# HVIBDC.net
KiCad netlist of a schematic drawn in EAGLE
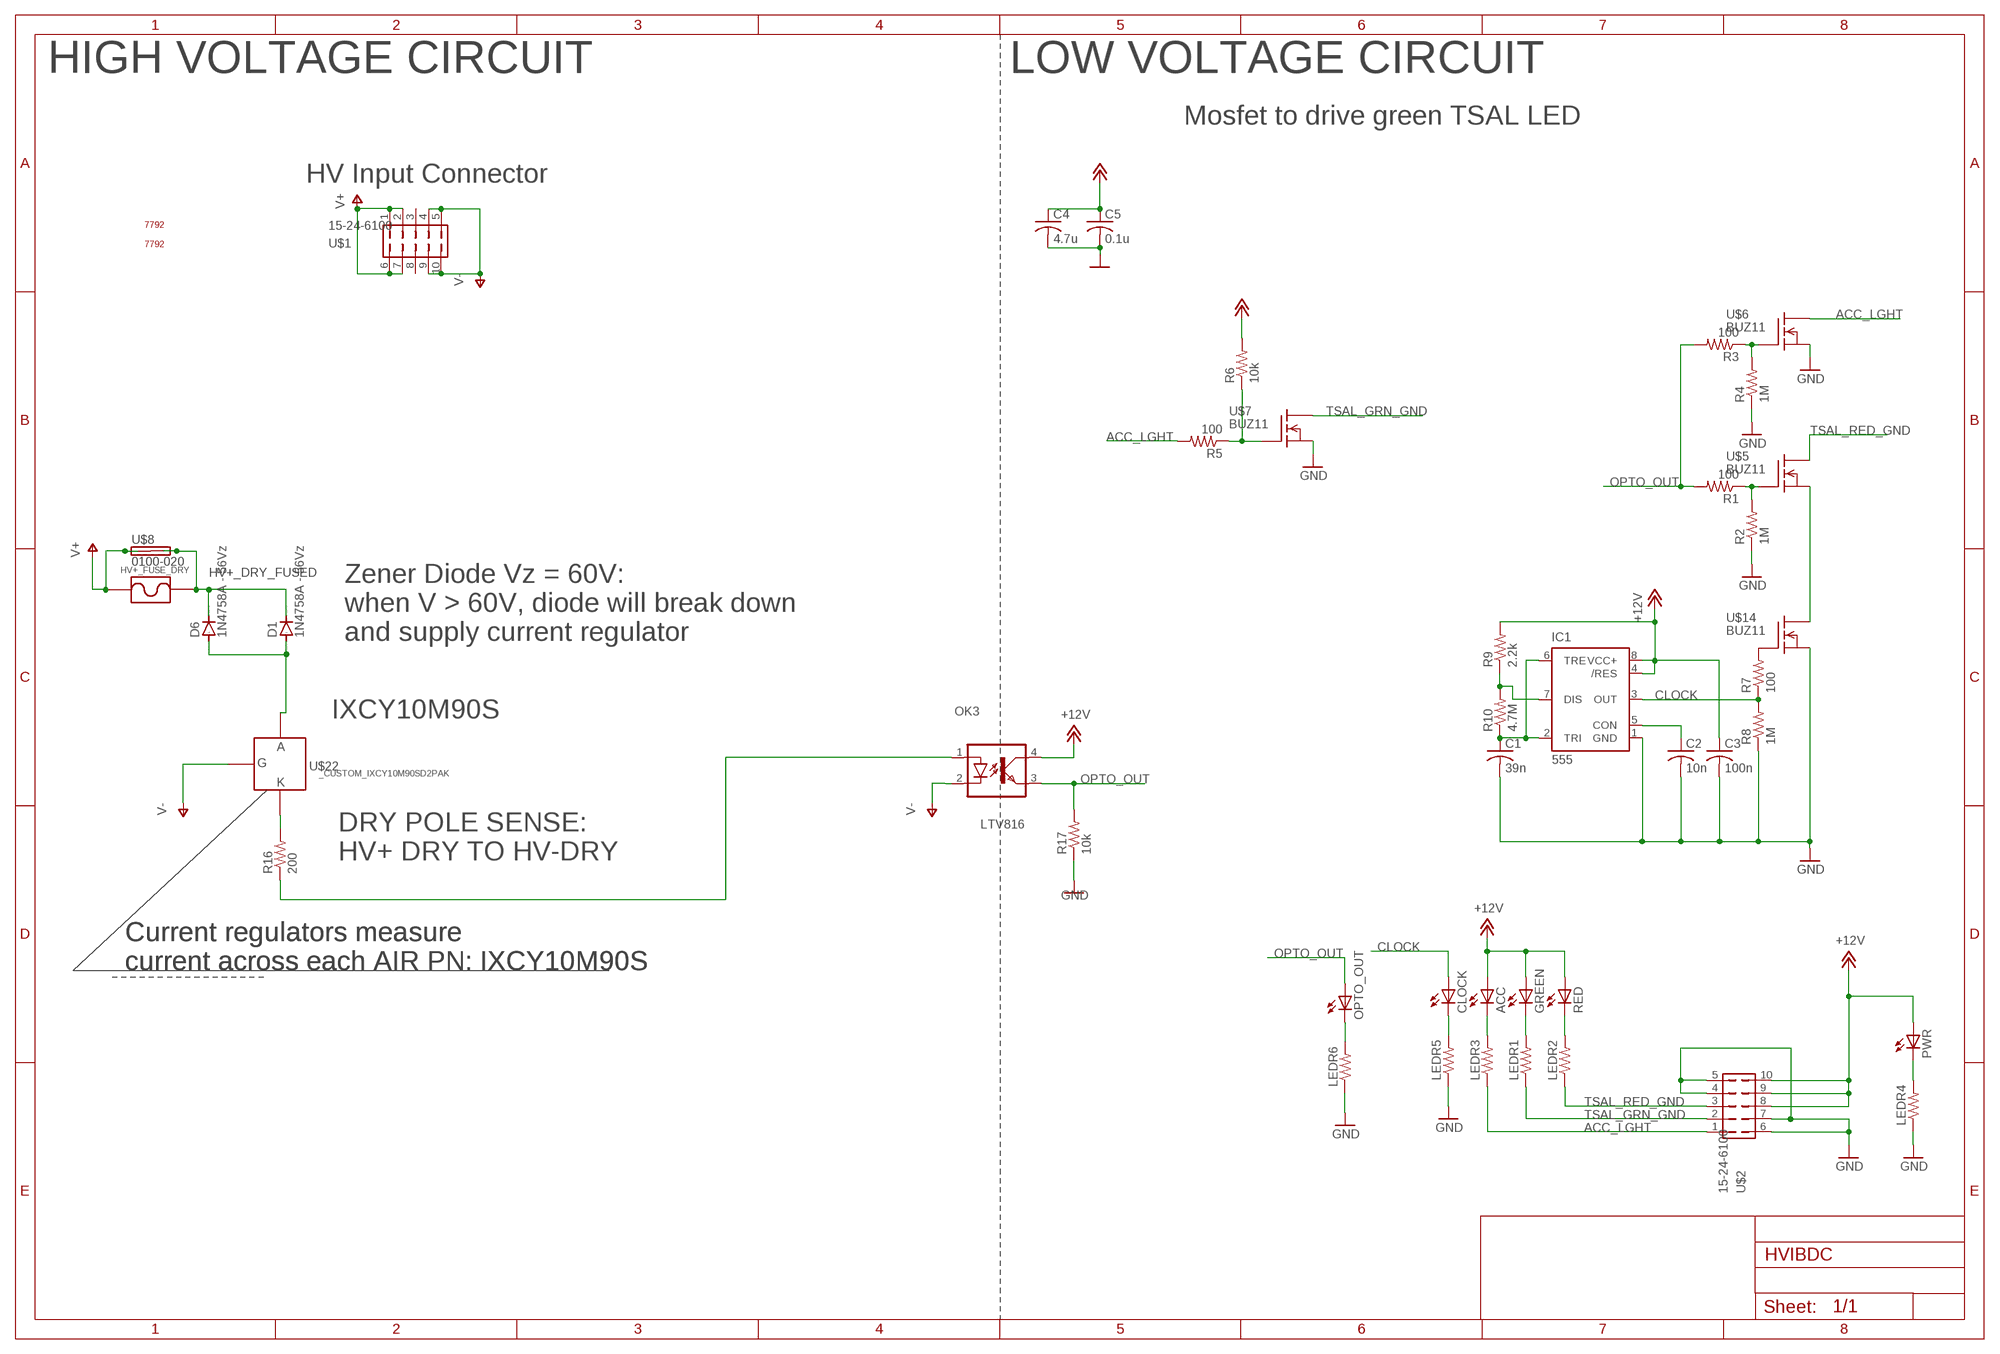
[diagram p0: schematic, sheet 1]

(export (version "E")
  (design (tool "Eeschema 10.0.6"))
  (components
    (comp (ref "ACC")
      (value "LEDCHIPLED_0805")
      (footprint "eagle-import:CHIPLED_0805")
      (libsource (lib "eagle-import") (part "LEDCHIPLED_0805"))
    )
    (comp (ref "C1")
      (value "39n")
      (footprint "eagle-import:C0805")
      (libsource (lib "eagle-import") (part "C-USC0805"))
    )
    (comp (ref "C2")
      (value "10n")
      (footprint "eagle-import:C0805")
      (libsource (lib "eagle-import") (part "C-USC0805"))
    )
    (comp (ref "C3")
      (value "100n")
      (footprint "eagle-import:C0805")
      (libsource (lib "eagle-import") (part "C-USC0805"))
    )
    (comp (ref "C4")
      (value "4.7u")
      (footprint "eagle-import:C0805")
      (libsource (lib "eagle-import") (part "C-USC0805"))
    )
    (comp (ref "C5")
      (value "0.1u")
      (footprint "eagle-import:C0805")
      (libsource (lib "eagle-import") (part "C-USC0805"))
    )
    (comp (ref "CLOCK")
      (value "LEDCHIPLED_0805")
      (footprint "eagle-import:CHIPLED_0805")
      (libsource (lib "eagle-import") (part "LEDCHIPLED_0805"))
    )
    (comp (ref "D1")
      (value "1N4758A - 56Vz")
      (footprint "eagle-import:DO201-15")
      (libsource (lib "eagle-import") (part "1N5624"))
    )
    (comp (ref "D6")
      (value "1N4758A - 56Vz")
      (footprint "eagle-import:DO201-15")
      (libsource (lib "eagle-import") (part "1N5624"))
    )
    (comp (ref "GREEN")
      (value "LEDCHIPLED_0805")
      (footprint "eagle-import:CHIPLED_0805")
      (libsource (lib "eagle-import") (part "LEDCHIPLED_0805"))
    )
    (comp (ref "HV+_FUSE_DRY")
      (value "_CUSTOM_PARTS_LF_885")
      (footprint "eagle-import:_CUSTOM_PARTS_LF_885")
      (libsource (lib "eagle-import") (part "_CUSTOM_PARTS_LF_885"))
    )
    (comp (ref "IC1")
      (value "555")
      (footprint "eagle-import:DIP08")
      (libsource (lib "eagle-import") (part "555P"))
    )
    (comp (ref "LEDR1")
      (value "R-US_R0805")
      (footprint "eagle-import:R0805")
      (libsource (lib "eagle-import") (part "R-US_R0805"))
    )
    (comp (ref "LEDR2")
      (value "R-US_R0805")
      (footprint "eagle-import:R0805")
      (libsource (lib "eagle-import") (part "R-US_R0805"))
    )
    (comp (ref "LEDR3")
      (value "R-US_R0805")
      (footprint "eagle-import:R0805")
      (libsource (lib "eagle-import") (part "R-US_R0805"))
    )
    (comp (ref "LEDR4")
      (value "R-US_R0805")
      (footprint "eagle-import:R0805")
      (libsource (lib "eagle-import") (part "R-US_R0805"))
    )
    (comp (ref "LEDR5")
      (value "R-US_R0805")
      (footprint "eagle-import:R0805")
      (libsource (lib "eagle-import") (part "R-US_R0805"))
    )
    (comp (ref "LEDR6")
      (value "R-US_R0805")
      (footprint "eagle-import:R0805")
      (libsource (lib "eagle-import") (part "R-US_R0805"))
    )
    (comp (ref "OK3")
      (value "LTV816")
      (footprint "eagle-import:DIL04")
      (libsource (lib "eagle-import") (part "LTV816"))
    )
    (comp (ref "OPTO_OUT")
      (value "LEDCHIPLED_0805")
      (footprint "eagle-import:CHIPLED_0805")
      (libsource (lib "eagle-import") (part "LEDCHIPLED_0805"))
    )
    (comp (ref "PWR")
      (value "LEDCHIPLED_0805")
      (footprint "eagle-import:CHIPLED_0805")
      (libsource (lib "eagle-import") (part "LEDCHIPLED_0805"))
    )
    (comp (ref "R1")
      (value "100")
      (footprint "eagle-import:R0805")
      (libsource (lib "eagle-import") (part "resistor_348_R-US_R0805"))
    )
    (comp (ref "R2")
      (value "1M")
      (footprint "eagle-import:R0805")
      (libsource (lib "eagle-import") (part "resistor_348_R-US_R0805"))
    )
    (comp (ref "R3")
      (value "100")
      (footprint "eagle-import:R0805")
      (libsource (lib "eagle-import") (part "resistor_348_R-US_R0805"))
    )
    (comp (ref "R4")
      (value "1M")
      (footprint "eagle-import:R0805")
      (libsource (lib "eagle-import") (part "resistor_348_R-US_R0805"))
    )
    (comp (ref "R5")
      (value "100")
      (footprint "eagle-import:R0805")
      (libsource (lib "eagle-import") (part "resistor_348_R-US_R0805"))
    )
    (comp (ref "R6")
      (value "10k")
      (footprint "eagle-import:R0805")
      (libsource (lib "eagle-import") (part "resistor_348_R-US_R0805"))
    )
    (comp (ref "R7")
      (value "100")
      (footprint "eagle-import:R0805")
      (libsource (lib "eagle-import") (part "resistor_348_R-US_R0805"))
    )
    (comp (ref "R8")
      (value "1M")
      (footprint "eagle-import:R0805")
      (libsource (lib "eagle-import") (part "resistor_348_R-US_R0805"))
    )
    (comp (ref "R9")
      (value "2.2k")
      (footprint "eagle-import:R0805")
      (libsource (lib "eagle-import") (part "resistor_348_R-US_R0805"))
    )
    (comp (ref "R10")
      (value "4.7M")
      (footprint "eagle-import:R0805")
      (libsource (lib "eagle-import") (part "resistor_348_R-US_R0805"))
    )
    (comp (ref "R16")
      (value "200")
      (footprint "eagle-import:R2010")
      (libsource (lib "eagle-import") (part "Main_14107900_R-US_R2010"))
    )
    (comp (ref "R17")
      (value "10k")
      (footprint "eagle-import:R0805")
      (libsource (lib "eagle-import") (part "resistor_348_R-US_R0805"))
    )
    (comp (ref "RED")
      (value "LEDCHIPLED_0805")
      (footprint "eagle-import:CHIPLED_0805")
      (libsource (lib "eagle-import") (part "LEDCHIPLED_0805"))
    )
    (comp (ref "U$1")
      (value "15-24-6100")
      (footprint "eagle-import:15-24-6100")
      (libsource (lib "eagle-import") (part "15-24-6100"))
    )
    (comp (ref "U$2")
      (value "15-24-6100")
      (footprint "eagle-import:15-24-6100")
      (libsource (lib "eagle-import") (part "15-24-6100"))
    )
    (comp (ref "U$3")
      (value "7792")
      (footprint "eagle-import:7792")
      (libsource (lib "eagle-import") (part "7792"))
    )
    (comp (ref "U$4")
      (value "7792")
      (footprint "eagle-import:7792")
      (libsource (lib "eagle-import") (part "7792"))
    )
    (comp (ref "U$5")
      (value "BUZ11")
      (footprint "eagle-import:TO220")
      (libsource (lib "eagle-import") (part "BUZ11"))
    )
    (comp (ref "U$6")
      (value "BUZ11")
      (footprint "eagle-import:TO220")
      (libsource (lib "eagle-import") (part "BUZ11"))
    )
    (comp (ref "U$7")
      (value "BUZ11")
      (footprint "eagle-import:TO220")
      (libsource (lib "eagle-import") (part "BUZ11"))
    )
    (comp (ref "U$8")
      (value "0100-020")
      (footprint "eagle-import:0100-020")
      (libsource (lib "eagle-import") (part "0100-020"))
    )
    (comp (ref "U$14")
      (value "BUZ11")
      (footprint "eagle-import:TO220")
      (libsource (lib "eagle-import") (part "BUZ11"))
    )
    (comp (ref "U$22")
      (value "_CUSTOM_IXCY10M90SD2PAK")
      (footprint "eagle-import:TO228P991X238-3")
      (libsource (lib "eagle-import") (part "_CUSTOM_IXCY10M90SD2PAK"))
    )
  )
  (nets
    (net (code "1") (name "+12V") (class "Default")
      (node (ref "ACC") (pin "A") (pinfunction "A_A") (pintype "passive"))
      (node (ref "C3") (pin "1") (pinfunction "1_1") (pintype "passive"))
      (node (ref "C4") (pin "1") (pinfunction "1_1") (pintype "passive"))
      (node (ref "C5") (pin "1") (pinfunction "1_1") (pintype "passive"))
      (node (ref "GREEN") (pin "A") (pinfunction "A_A") (pintype "passive"))
      (node (ref "IC1") (pin "4") (pinfunction "/RES_4") (pintype "input"))
      (node (ref "IC1") (pin "8") (pinfunction "VCC+_8") (pintype "power_in"))
      (node (ref "OK3") (pin "4") (pinfunction "COL_4") (pintype "passive"))
      (node (ref "PWR") (pin "A") (pinfunction "A_A") (pintype "passive"))
      (node (ref "R6") (pin "2") (pinfunction "2_2") (pintype "passive"))
      (node (ref "R9") (pin "2") (pinfunction "2_2") (pintype "passive"))
      (node (ref "RED") (pin "A") (pinfunction "A_A") (pintype "passive"))
      (node (ref "U$2") (pin "10") (pinfunction "10_10") (pintype "passive"))
      (node (ref "U$2") (pin "8") (pinfunction "8_8") (pintype "passive"))
      (node (ref "U$2") (pin "9") (pinfunction "9_9") (pintype "passive"))
    )
    (net (code "2") (name "/ACC_LGHT") (class "Default")
      (node (ref "LEDR3") (pin "1") (pinfunction "1_1") (pintype "passive"))
      (node (ref "R5") (pin "2") (pinfunction "2_2") (pintype "passive"))
      (node (ref "U$2") (pin "1") (pinfunction "1_1") (pintype "passive"))
      (node (ref "U$6") (pin "2") (pinfunction "D_2") (pintype "passive"))
    )
    (net (code "3") (name "/CLOCK") (class "Default")
      (node (ref "CLOCK") (pin "A") (pinfunction "A_A") (pintype "passive"))
      (node (ref "IC1") (pin "3") (pinfunction "OUT_3") (pintype "output"))
      (node (ref "R7") (pin "1") (pinfunction "1_1") (pintype "passive"))
      (node (ref "R8") (pin "2") (pinfunction "2_2") (pintype "passive"))
    )
    (net (code "4") (name "/HV+_DRY_FUSED") (class "Default")
      (node (ref "D1") (pin "C") (pinfunction "C_C") (pintype "passive"))
      (node (ref "D6") (pin "C") (pinfunction "C_C") (pintype "passive"))
      (node (ref "HV+_FUSE_DRY") (pin "P$1") (pinfunction "P$1_P$1") (pintype "bidirectional"))
      (node (ref "U$8") (pin "P$2") (pinfunction "2A_P$2") (pintype "passive"))
      (node (ref "U$8") (pin "P$4") (pinfunction "2B_P$4") (pintype "passive"))
    )
    (net (code "5") (name "/OPTO_OUT") (class "Default")
      (node (ref "OK3") (pin "3") (pinfunction "EMIT_3") (pintype "passive"))
      (node (ref "OPTO_OUT") (pin "A") (pinfunction "A_A") (pintype "passive"))
      (node (ref "R1") (pin "2") (pinfunction "2_2") (pintype "passive"))
      (node (ref "R17") (pin "2") (pinfunction "2_2") (pintype "passive"))
      (node (ref "R3") (pin "2") (pinfunction "2_2") (pintype "passive"))
    )
    (net (code "6") (name "/TSAL_GRN_GND") (class "Default")
      (node (ref "LEDR1") (pin "1") (pinfunction "1_1") (pintype "passive"))
      (node (ref "U$2") (pin "2") (pinfunction "2_2") (pintype "passive"))
      (node (ref "U$7") (pin "2") (pinfunction "D_2") (pintype "passive"))
    )
    (net (code "7") (name "/TSAL_RED_GND") (class "Default")
      (node (ref "LEDR2") (pin "1") (pinfunction "1_1") (pintype "passive"))
      (node (ref "U$2") (pin "3") (pinfunction "3_3") (pintype "passive"))
      (node (ref "U$5") (pin "2") (pinfunction "D_2") (pintype "passive"))
    )
    (net (code "8") (name "GND") (class "Default")
      (node (ref "C1") (pin "2") (pinfunction "2_2") (pintype "passive"))
      (node (ref "C2") (pin "2") (pinfunction "2_2") (pintype "passive"))
      (node (ref "C3") (pin "2") (pinfunction "2_2") (pintype "passive"))
      (node (ref "C4") (pin "2") (pinfunction "2_2") (pintype "passive"))
      (node (ref "C5") (pin "2") (pinfunction "2_2") (pintype "passive"))
      (node (ref "IC1") (pin "1") (pinfunction "GND_1") (pintype "power_in"))
      (node (ref "LEDR4") (pin "1") (pinfunction "1_1") (pintype "passive"))
      (node (ref "LEDR5") (pin "1") (pinfunction "1_1") (pintype "passive"))
      (node (ref "LEDR6") (pin "1") (pinfunction "1_1") (pintype "passive"))
      (node (ref "R17") (pin "1") (pinfunction "1_1") (pintype "passive"))
      (node (ref "R2") (pin "1") (pinfunction "1_1") (pintype "passive"))
      (node (ref "R4") (pin "1") (pinfunction "1_1") (pintype "passive"))
      (node (ref "R8") (pin "1") (pinfunction "1_1") (pintype "passive"))
      (node (ref "U$14") (pin "3") (pinfunction "S_3") (pintype "passive"))
      (node (ref "U$2") (pin "4") (pinfunction "4_4") (pintype "passive"))
      (node (ref "U$2") (pin "5") (pinfunction "5_5") (pintype "passive"))
      (node (ref "U$2") (pin "6") (pinfunction "6_6") (pintype "passive"))
      (node (ref "U$2") (pin "7") (pinfunction "7_7") (pintype "passive"))
      (node (ref "U$6") (pin "3") (pinfunction "S_3") (pintype "passive"))
      (node (ref "U$7") (pin "3") (pinfunction "S_3") (pintype "passive"))
    )
    (net (code "9") (name "Net-(ACC-PadC)") (class "Default")
      (node (ref "ACC") (pin "C") (pinfunction "C_C") (pintype "passive"))
      (node (ref "LEDR3") (pin "2") (pinfunction "2_2") (pintype "passive"))
    )
    (net (code "10") (name "Net-(CLOCK-PadC)") (class "Default")
      (node (ref "CLOCK") (pin "C") (pinfunction "C_C") (pintype "passive"))
      (node (ref "LEDR5") (pin "2") (pinfunction "2_2") (pintype "passive"))
    )
    (net (code "11") (name "Net-(GREEN-PadC)") (class "Default")
      (node (ref "GREEN") (pin "C") (pinfunction "C_C") (pintype "passive"))
      (node (ref "LEDR1") (pin "2") (pinfunction "2_2") (pintype "passive"))
    )
    (net (code "12") (name "Net-(IC1-CON)") (class "Default")
      (node (ref "C2") (pin "1") (pinfunction "1_1") (pintype "passive"))
      (node (ref "IC1") (pin "5") (pinfunction "CON_5") (pintype "input"))
    )
    (net (code "13") (name "Net-(IC1-DIS)") (class "Default")
      (node (ref "IC1") (pin "7") (pinfunction "DIS_7") (pintype "input"))
      (node (ref "R10") (pin "2") (pinfunction "2_2") (pintype "passive"))
      (node (ref "R9") (pin "1") (pinfunction "1_1") (pintype "passive"))
    )
    (net (code "14") (name "Net-(IC1-TRE)") (class "Default")
      (node (ref "C1") (pin "1") (pinfunction "1_1") (pintype "passive"))
      (node (ref "IC1") (pin "2") (pinfunction "TRI_2") (pintype "input"))
      (node (ref "IC1") (pin "6") (pinfunction "TRE_6") (pintype "input"))
      (node (ref "R10") (pin "1") (pinfunction "1_1") (pintype "passive"))
    )
    (net (code "15") (name "Net-(LEDR2-Pad2)") (class "Default")
      (node (ref "LEDR2") (pin "2") (pinfunction "2_2") (pintype "passive"))
      (node (ref "RED") (pin "C") (pinfunction "C_C") (pintype "passive"))
    )
    (net (code "16") (name "Net-(LEDR4-Pad2)") (class "Default")
      (node (ref "LEDR4") (pin "2") (pinfunction "2_2") (pintype "passive"))
      (node (ref "PWR") (pin "C") (pinfunction "C_C") (pintype "passive"))
    )
    (net (code "17") (name "Net-(LEDR6-Pad2)") (class "Default")
      (node (ref "LEDR6") (pin "2") (pinfunction "2_2") (pintype "passive"))
      (node (ref "OPTO_OUT") (pin "C") (pinfunction "C_C") (pintype "passive"))
    )
    (net (code "18") (name "Net-(OK3-A)") (class "Default")
      (node (ref "OK3") (pin "1") (pinfunction "A_1") (pintype "passive"))
      (node (ref "R16") (pin "1") (pinfunction "1_1") (pintype "passive"))
    )
    (net (code "19") (name "Net-(U$5-G)") (class "Default")
      (node (ref "R1") (pin "1") (pinfunction "1_1") (pintype "passive"))
      (node (ref "R2") (pin "2") (pinfunction "2_2") (pintype "passive"))
      (node (ref "U$5") (pin "1") (pinfunction "G_1") (pintype "passive"))
    )
    (net (code "20") (name "Net-(U$6-G)") (class "Default")
      (node (ref "R3") (pin "1") (pinfunction "1_1") (pintype "passive"))
      (node (ref "R4") (pin "2") (pinfunction "2_2") (pintype "passive"))
      (node (ref "U$6") (pin "1") (pinfunction "G_1") (pintype "passive"))
    )
    (net (code "21") (name "Net-(U$7-G)") (class "Default")
      (node (ref "R5") (pin "1") (pinfunction "1_1") (pintype "passive"))
      (node (ref "R6") (pin "1") (pinfunction "1_1") (pintype "passive"))
      (node (ref "U$7") (pin "1") (pinfunction "G_1") (pintype "passive"))
    )
    (net (code "22") (name "Net-(U$14-D)") (class "Default")
      (node (ref "U$14") (pin "2") (pinfunction "D_2") (pintype "passive"))
      (node (ref "U$5") (pin "3") (pinfunction "S_3") (pintype "passive"))
    )
    (net (code "23") (name "Net-(U$14-G)") (class "Default")
      (node (ref "R7") (pin "2") (pinfunction "2_2") (pintype "passive"))
      (node (ref "U$14") (pin "1") (pinfunction "G_1") (pintype "passive"))
    )
    (net (code "24") (name "Net-(U$22-A)") (class "Default")
      (node (ref "D1") (pin "A") (pinfunction "A_A") (pintype "passive"))
      (node (ref "D6") (pin "A") (pinfunction "A_A") (pintype "passive"))
      (node (ref "U$22") (pin "3") (pinfunction "A_3") (pintype "bidirectional"))
    )
    (net (code "25") (name "Net-(U$22-K)") (class "Default")
      (node (ref "R16") (pin "2") (pinfunction "2_2") (pintype "passive"))
      (node (ref "U$22") (pin "2") (pinfunction "K_2") (pintype "bidirectional"))
    )
    (net (code "26") (name "V+") (class "Default")
      (node (ref "HV+_FUSE_DRY") (pin "P$2") (pinfunction "P$2_P$2") (pintype "bidirectional"))
      (node (ref "U$1") (pin "1") (pinfunction "1_1") (pintype "passive"))
      (node (ref "U$1") (pin "2") (pinfunction "2_2") (pintype "passive"))
      (node (ref "U$1") (pin "6") (pinfunction "6_6") (pintype "passive"))
      (node (ref "U$1") (pin "7") (pinfunction "7_7") (pintype "passive"))
      (node (ref "U$8") (pin "P$1") (pinfunction "1A_P$1") (pintype "passive"))
      (node (ref "U$8") (pin "P$3") (pinfunction "1B_P$3") (pintype "passive"))
    )
    (net (code "27") (name "V-") (class "Default")
      (node (ref "OK3") (pin "2") (pinfunction "C_2") (pintype "passive"))
      (node (ref "U$1") (pin "10") (pinfunction "10_10") (pintype "passive"))
      (node (ref "U$1") (pin "4") (pinfunction "4_4") (pintype "passive"))
      (node (ref "U$1") (pin "5") (pinfunction "5_5") (pintype "passive"))
      (node (ref "U$1") (pin "9") (pinfunction "9_9") (pintype "passive"))
      (node (ref "U$22") (pin "1") (pinfunction "G_1") (pintype "bidirectional"))
    )
    (net (code "28") (name "unconnected-(U$1-Pad3)") (class "Default")
      (node (ref "U$1") (pin "3") (pinfunction "3_3") (pintype "passive"))
    )
    (net (code "29") (name "unconnected-(U$1-Pad8)") (class "Default")
      (node (ref "U$1") (pin "8") (pinfunction "8_8") (pintype "passive"))
    )
  )
)
